# Connectors.net
KiCad netlist of a schematic drawn in Altium Designer
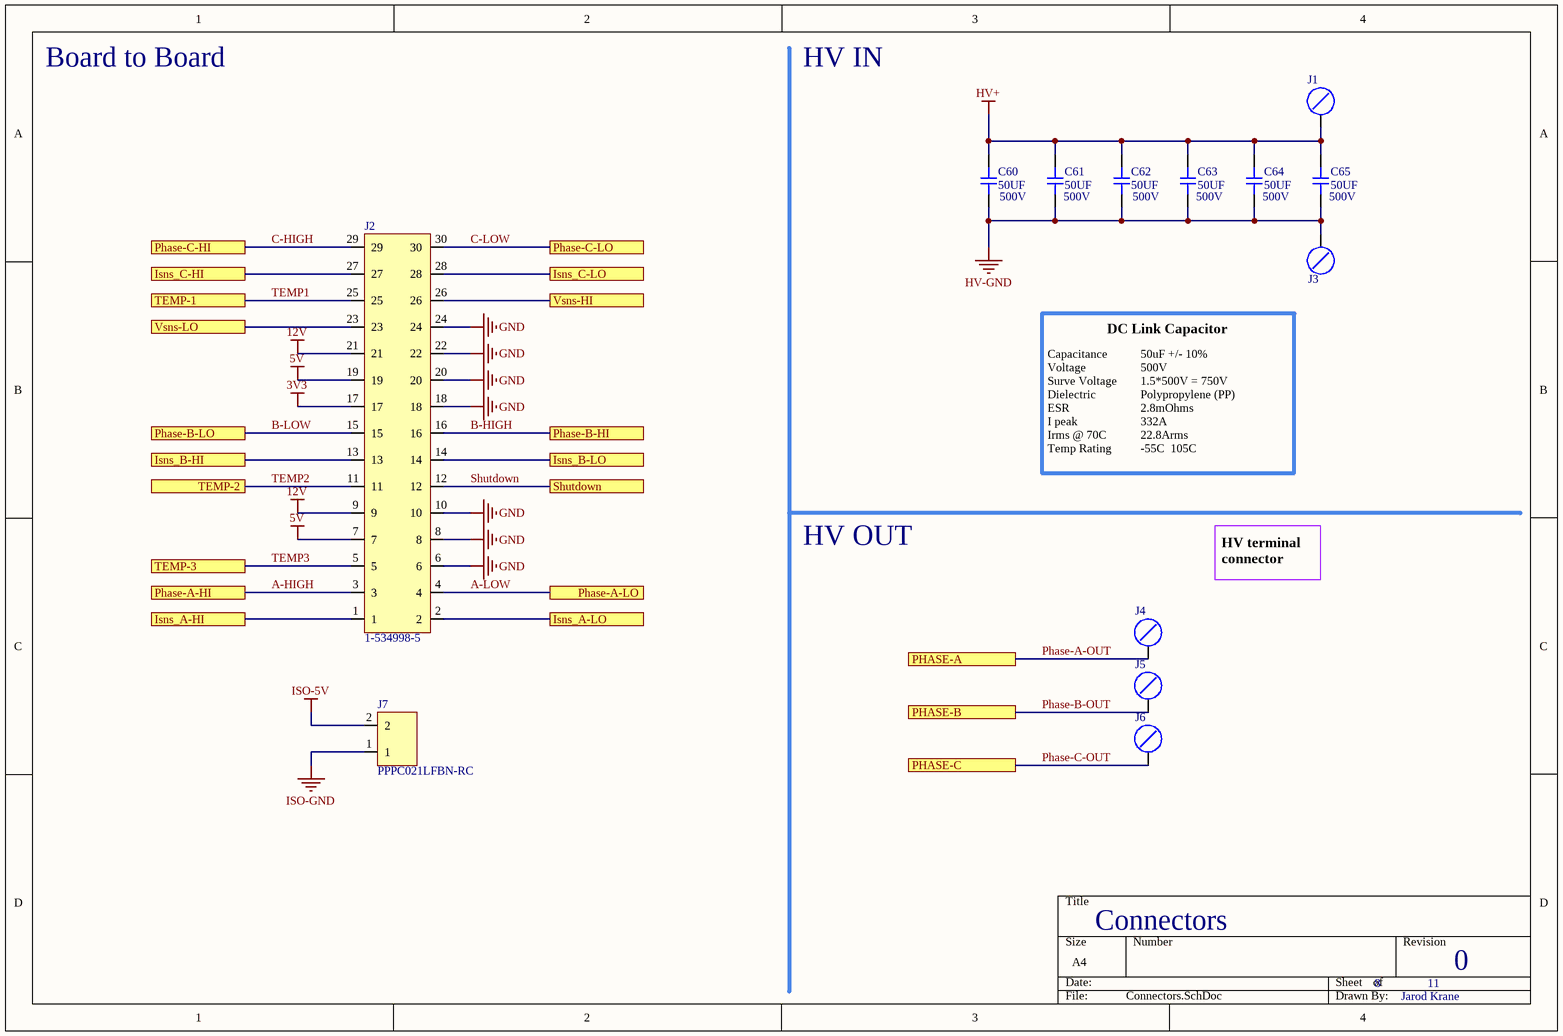
[diagram p0: Connectors.SchDoc]

(export (version "E")
  (design (tool "Eeschema 10.0.6"))
  (components
    (comp (ref "C60")
      (value "50UF")
      (footprint "DCLINKCAP")
      (description "CAP FILM 50UF 10% 500VDC RADIAL")
      (fields
        (field (name "MANUFACTURER") "KEMET")
        (field (name "MANUFACTURER PART NUMBER") "C4AQLBW5500A3JK")
        (field (name "VOLTAGE RATING (DC)") "500V")
      )
      (libsource (lib "InverterSCHLib") (part "50UF-500V"))
    )
    (comp (ref "C61")
      (value "50UF")
      (footprint "DCLINKCAP")
      (description "CAP FILM 50UF 10% 500VDC RADIAL")
      (fields
        (field (name "MANUFACTURER") "KEMET")
        (field (name "MANUFACTURER PART NUMBER") "C4AQLBW5500A3JK")
        (field (name "VOLTAGE RATING (DC)") "500V")
      )
      (libsource (lib "InverterSCHLib") (part "50UF-500V"))
    )
    (comp (ref "C62")
      (value "50UF")
      (footprint "DCLINKCAP")
      (description "CAP FILM 50UF 10% 500VDC RADIAL")
      (fields
        (field (name "MANUFACTURER") "KEMET")
        (field (name "MANUFACTURER PART NUMBER") "C4AQLBW5500A3JK")
        (field (name "VOLTAGE RATING (DC)") "500V")
      )
      (libsource (lib "InverterSCHLib") (part "50UF-500V"))
    )
    (comp (ref "C63")
      (value "50UF")
      (footprint "DCLINKCAP")
      (description "CAP FILM 50UF 10% 500VDC RADIAL")
      (fields
        (field (name "MANUFACTURER") "KEMET")
        (field (name "MANUFACTURER PART NUMBER") "C4AQLBW5500A3JK")
        (field (name "VOLTAGE RATING (DC)") "500V")
      )
      (libsource (lib "InverterSCHLib") (part "50UF-500V"))
    )
    (comp (ref "C64")
      (value "50UF")
      (footprint "DCLINKCAP")
      (description "CAP FILM 50UF 10% 500VDC RADIAL")
      (fields
        (field (name "MANUFACTURER") "KEMET")
        (field (name "MANUFACTURER PART NUMBER") "C4AQLBW5500A3JK")
        (field (name "VOLTAGE RATING (DC)") "500V")
      )
      (libsource (lib "InverterSCHLib") (part "50UF-500V"))
    )
    (comp (ref "C65")
      (value "50UF")
      (footprint "DCLINKCAP")
      (description "CAP FILM 50UF 10% 500VDC RADIAL")
      (fields
        (field (name "MANUFACTURER") "KEMET")
        (field (name "MANUFACTURER PART NUMBER") "C4AQLBW5500A3JK")
        (field (name "VOLTAGE RATING (DC)") "500V")
      )
      (libsource (lib "InverterSCHLib") (part "50UF-500V"))
    )
    (comp (ref "J1")
      (value "M8 Terminal")
      (footprint "M8 Terminal")
      (description "M8 Screw terminal for HV connections")
      (libsource (lib "InverterSCHLib") (part "M8 Terminal"))
    )
    (comp (ref "J2")
      (value "1-534998-5")
      (footprint "CONN POS-F")
      (description "30 Position Receptacle Connector 0.100\" (2.54mm) Through Hole Gold")
      (fields (field (name "MANUFACTURER") "TE Connectivity"))
      (libsource (lib "InverterSCHLib") (part "CONN-30POS-F"))
    )
    (comp (ref "J3")
      (value "M8 Terminal")
      (footprint "M8 Terminal")
      (description "M8 Screw terminal for HV connections")
      (libsource (lib "InverterSCHLib") (part "M8 Terminal"))
    )
    (comp (ref "J4")
      (value "M8 Terminal")
      (footprint "M8 Terminal")
      (description "M8 Screw terminal for HV connections")
      (libsource (lib "InverterSCHLib") (part "M8 Terminal"))
    )
    (comp (ref "J5")
      (value "M8 Terminal")
      (footprint "M8 Terminal")
      (description "M8 Screw terminal for HV connections")
      (libsource (lib "InverterSCHLib") (part "M8 Terminal"))
    )
    (comp (ref "J6")
      (value "M8 Terminal")
      (footprint "M8 Terminal")
      (description "M8 Screw terminal for HV connections")
      (libsource (lib "InverterSCHLib") (part "M8 Terminal"))
    )
    (comp (ref "J7")
      (value "PPPC021LFBN-RC")
      (footprint "CONN-2POS-F")
      (description "CONN HDR 2POS 0.1 GOLD PCB")
      (fields (field (name "MANUFACTURER") "Sullins"))
      (libsource (lib "InverterSCHLib") (part "CONN-2POS-F"))
    )
  )
  (nets
    (net (code "1") (name "/A-HIGH") (class "Default")
      (node (ref "J2") (pin "3") (pinfunction "3_3") (pintype "passive"))
    )
    (net (code "2") (name "/A-LOW") (class "Default")
      (node (ref "J2") (pin "4") (pinfunction "4_4") (pintype "passive"))
    )
    (net (code "3") (name "/B-HIGH") (class "Default")
      (node (ref "J2") (pin "16") (pinfunction "16_16") (pintype "passive"))
    )
    (net (code "4") (name "/B-LOW") (class "Default")
      (node (ref "J2") (pin "15") (pinfunction "15_15") (pintype "passive"))
    )
    (net (code "5") (name "/C-HIGH") (class "Default")
      (node (ref "J2") (pin "29") (pinfunction "29_29") (pintype "passive"))
    )
    (net (code "6") (name "/C-LOW") (class "Default")
      (node (ref "J2") (pin "30") (pinfunction "30_30") (pintype "passive"))
    )
    (net (code "7") (name "/Isns_A-HI") (class "Default")
      (node (ref "J2") (pin "1") (pinfunction "1_1") (pintype "passive"))
    )
    (net (code "8") (name "/Isns_A-LO") (class "Default")
      (node (ref "J2") (pin "2") (pinfunction "2_2") (pintype "passive"))
    )
    (net (code "9") (name "/Isns_B-HI") (class "Default")
      (node (ref "J2") (pin "13") (pinfunction "13_13") (pintype "passive"))
    )
    (net (code "10") (name "/Isns_B-LO") (class "Default")
      (node (ref "J2") (pin "14") (pinfunction "14_14") (pintype "passive"))
    )
    (net (code "11") (name "/Isns_C-HI") (class "Default")
      (node (ref "J2") (pin "27") (pinfunction "27_27") (pintype "passive"))
    )
    (net (code "12") (name "/Isns_C-LO") (class "Default")
      (node (ref "J2") (pin "28") (pinfunction "28_28") (pintype "passive"))
    )
    (net (code "13") (name "/Phase-A-OUT") (class "Default")
      (node (ref "J4") (pin "1") (pinfunction "1_1") (pintype "passive"))
    )
    (net (code "14") (name "/Phase-B-OUT") (class "Default")
      (node (ref "J5") (pin "1") (pinfunction "1_1") (pintype "passive"))
    )
    (net (code "15") (name "/Phase-C-OUT") (class "Default")
      (node (ref "J6") (pin "1") (pinfunction "1_1") (pintype "passive"))
    )
    (net (code "16") (name "/Shutdown") (class "Default")
      (node (ref "J2") (pin "12") (pinfunction "12_12") (pintype "passive"))
    )
    (net (code "17") (name "/TEMP1") (class "Default")
      (node (ref "J2") (pin "25") (pinfunction "25_25") (pintype "passive"))
    )
    (net (code "18") (name "/TEMP2") (class "Default")
      (node (ref "J2") (pin "11") (pinfunction "11_11") (pintype "passive"))
    )
    (net (code "19") (name "/TEMP3") (class "Default")
      (node (ref "J2") (pin "5") (pinfunction "5_5") (pintype "passive"))
    )
    (net (code "20") (name "/Vsns-HI") (class "Default")
      (node (ref "J2") (pin "26") (pinfunction "26_26") (pintype "passive"))
    )
    (net (code "21") (name "/Vsns-LO") (class "Default")
      (node (ref "J2") (pin "23") (pinfunction "23_23") (pintype "passive"))
    )
    (net (code "22") (name "3V3") (class "Default")
      (node (ref "J2") (pin "17") (pinfunction "17_17") (pintype "passive"))
    )
    (net (code "23") (name "5V") (class "Default")
      (node (ref "J2") (pin "19") (pinfunction "19_19") (pintype "passive"))
      (node (ref "J2") (pin "7") (pinfunction "7_7") (pintype "passive"))
    )
    (net (code "24") (name "12V") (class "Default")
      (node (ref "J2") (pin "21") (pinfunction "21_21") (pintype "passive"))
      (node (ref "J2") (pin "9") (pinfunction "9_9") (pintype "passive"))
    )
    (net (code "25") (name "GND") (class "Default")
      (node (ref "J2") (pin "10") (pinfunction "10_10") (pintype "passive"))
      (node (ref "J2") (pin "18") (pinfunction "18_18") (pintype "passive"))
      (node (ref "J2") (pin "20") (pinfunction "20_20") (pintype "passive"))
      (node (ref "J2") (pin "22") (pinfunction "22_22") (pintype "passive"))
      (node (ref "J2") (pin "24") (pinfunction "24_24") (pintype "passive"))
      (node (ref "J2") (pin "6") (pinfunction "6_6") (pintype "passive"))
      (node (ref "J2") (pin "8") (pinfunction "8_8") (pintype "passive"))
    )
    (net (code "26") (name "HV+") (class "Default")
      (node (ref "C60") (pin "2") (pinfunction "2_2") (pintype "passive"))
      (node (ref "C61") (pin "2") (pinfunction "2_2") (pintype "passive"))
      (node (ref "C62") (pin "2") (pinfunction "2_2") (pintype "passive"))
      (node (ref "C63") (pin "2") (pinfunction "2_2") (pintype "passive"))
      (node (ref "C64") (pin "2") (pinfunction "2_2") (pintype "passive"))
      (node (ref "C65") (pin "2") (pinfunction "2_2") (pintype "passive"))
      (node (ref "J1") (pin "1") (pinfunction "1_1") (pintype "passive"))
    )
    (net (code "27") (name "HV-GND") (class "Default")
      (node (ref "C60") (pin "1") (pinfunction "1_1") (pintype "passive"))
      (node (ref "C61") (pin "1") (pinfunction "1_1") (pintype "passive"))
      (node (ref "C62") (pin "1") (pinfunction "1_1") (pintype "passive"))
      (node (ref "C63") (pin "1") (pinfunction "1_1") (pintype "passive"))
      (node (ref "C64") (pin "1") (pinfunction "1_1") (pintype "passive"))
      (node (ref "C65") (pin "1") (pinfunction "1_1") (pintype "passive"))
      (node (ref "J3") (pin "1") (pinfunction "1_1") (pintype "passive"))
    )
    (net (code "28") (name "ISO-5V") (class "Default")
      (node (ref "J7") (pin "2") (pinfunction "2_2") (pintype "passive"))
    )
    (net (code "29") (name "ISO-GND") (class "Default")
      (node (ref "J7") (pin "1") (pinfunction "1_1") (pintype "passive"))
    )
  )
)
